# Laser_Teensy5.net
KiCad netlist of a schematic drawn in EAGLE
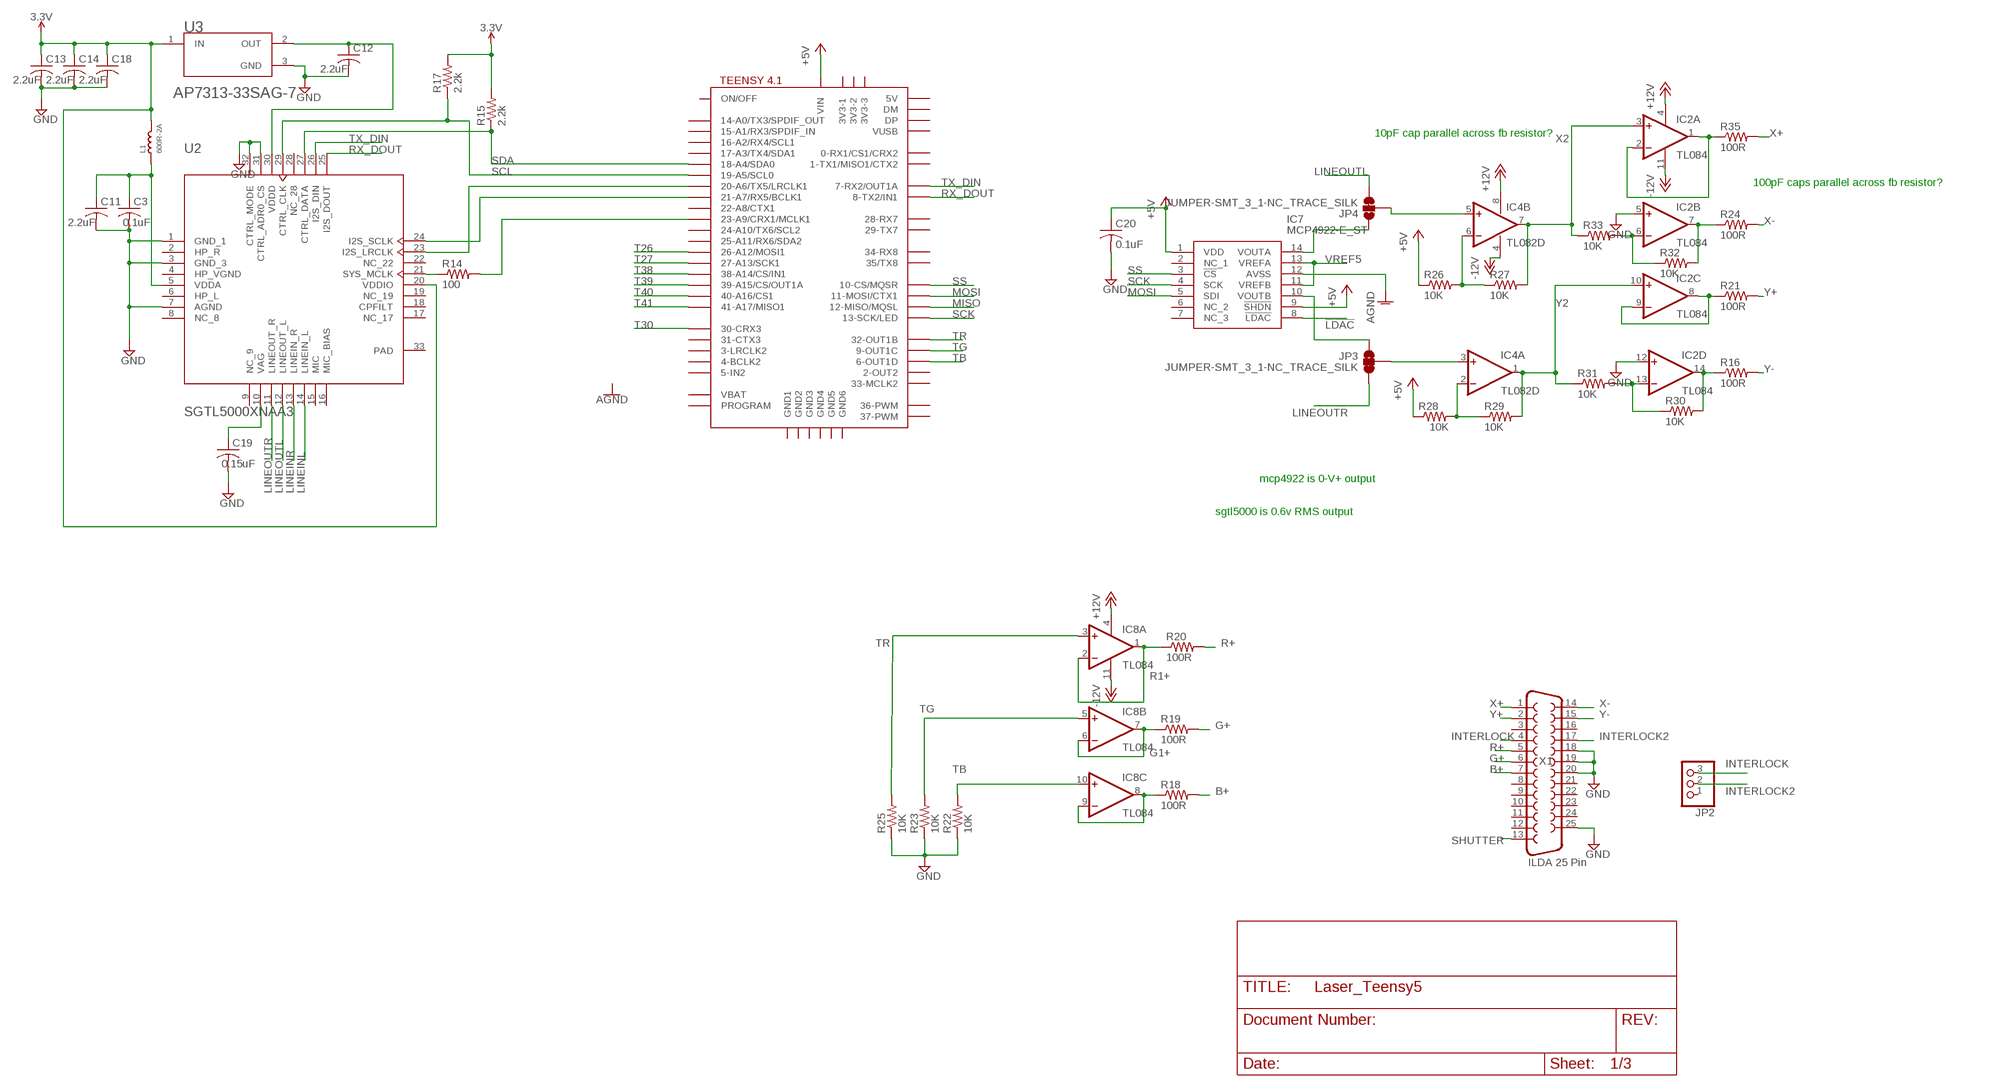
[diagram p0: schematic, sheet 1]
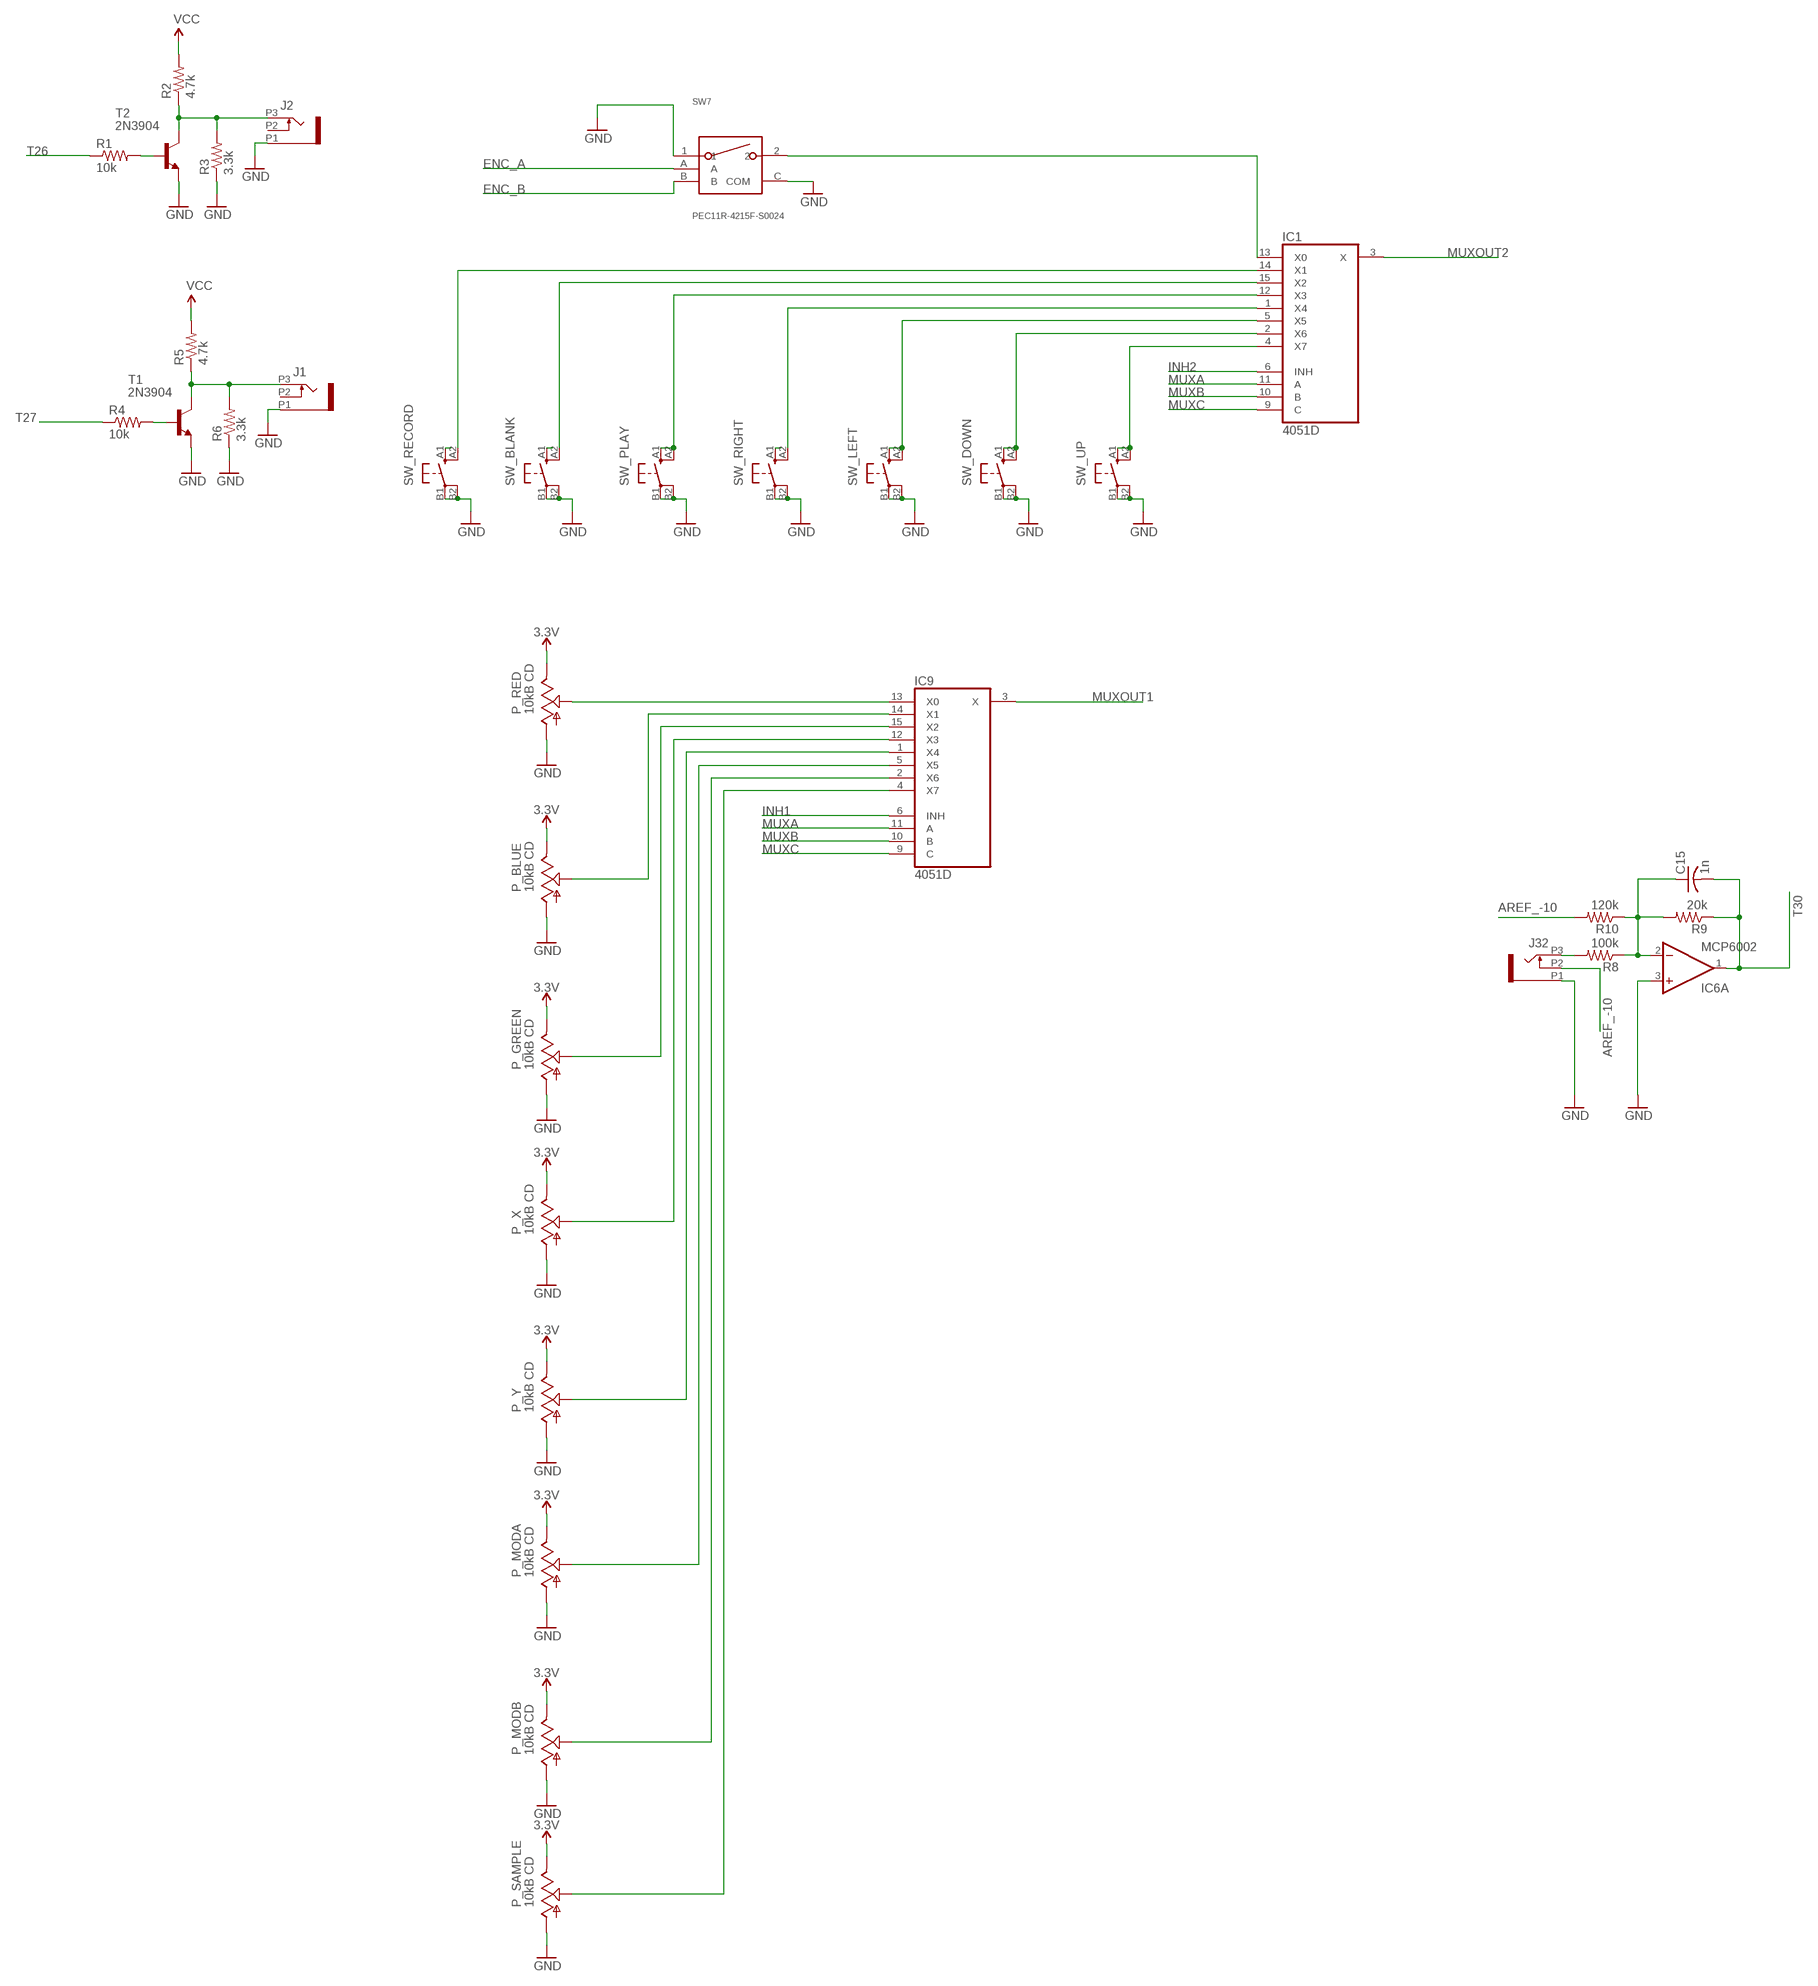
[diagram p1: schematic, sheet 2]
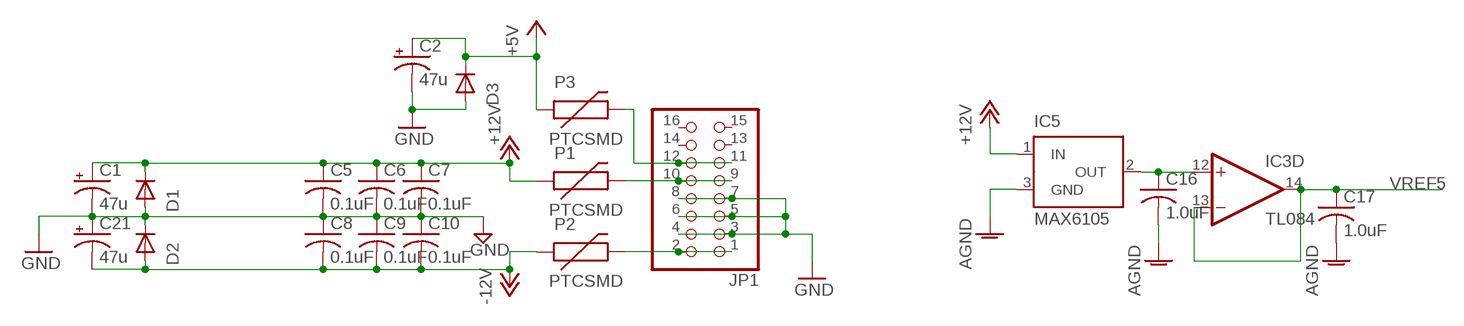
[diagram p2: schematic, sheet 3]

(export (version "E")
  (design (tool "Eeschema 10.0.6"))
  (components
    (comp (ref "C1")
      (value "47u")
      (footprint "eagle-import:PANASONIC_D")
      (libsource (lib "eagle-import") (part "CPOL-USD"))
    )
    (comp (ref "C2")
      (value "47u")
      (footprint "eagle-import:PANASONIC_D")
      (libsource (lib "eagle-import") (part "CPOL-USD"))
    )
    (comp (ref "C5")
      (value "0.1uF")
      (footprint "eagle-import:C0603")
      (libsource (lib "eagle-import") (part "C-USC0603"))
    )
    (comp (ref "C6")
      (value "0.1uF")
      (footprint "eagle-import:C0603")
      (libsource (lib "eagle-import") (part "C-USC0603"))
    )
    (comp (ref "C7")
      (value "0.1uF")
      (footprint "eagle-import:C0603")
      (libsource (lib "eagle-import") (part "C-USC0603"))
    )
    (comp (ref "C8")
      (value "0.1uF")
      (footprint "eagle-import:C0603")
      (libsource (lib "eagle-import") (part "C-USC0603"))
    )
    (comp (ref "C9")
      (value "0.1uF")
      (footprint "eagle-import:C0603")
      (libsource (lib "eagle-import") (part "C-USC0603"))
    )
    (comp (ref "C10")
      (value "0.1uF")
      (footprint "eagle-import:C0603")
      (libsource (lib "eagle-import") (part "C-USC0603"))
    )
    (comp (ref "C16")
      (value "1.0uF")
      (footprint "eagle-import:C025-024X044")
      (libsource (lib "eagle-import") (part "C-US025-024X044"))
    )
    (comp (ref "C17")
      (value "1.0uF")
      (footprint "eagle-import:C025-024X044")
      (libsource (lib "eagle-import") (part "C-US025-024X044"))
    )
    (comp (ref "C21")
      (value "47u")
      (footprint "eagle-import:PANASONIC_D")
      (libsource (lib "eagle-import") (part "CPOL-USD"))
    )
    (comp (ref "D1")
      (value "1N5819HW")
      (footprint "eagle-import:SOD123")
      (libsource (lib "eagle-import") (part "DIODE-SOD123"))
    )
    (comp (ref "D2")
      (value "1N5819HW")
      (footprint "eagle-import:SOD123")
      (libsource (lib "eagle-import") (part "DIODE-SOD123"))
    )
    (comp (ref "D3")
      (value "1N5819HW")
      (footprint "eagle-import:SOD123")
      (libsource (lib "eagle-import") (part "DIODE-SOD123"))
    )
    (comp (ref "IC3")
      (value "TL084")
      (footprint "eagle-import:SOIC-14")
      (libsource (lib "eagle-import") (part "TL084"))
    )
    (comp (ref "IC5")
      (value "MAX6105")
      (footprint "eagle-import:SOT23")
      (libsource (lib "eagle-import") (part "MAX6520"))
    )
    (comp (ref "JP1")
      (value "PINHD-2X8")
      (footprint "eagle-import:2X08")
      (libsource (lib "eagle-import") (part "PINHD-2X8"))
    )
    (comp (ref "P1")
      (value "PTCSMD")
      (footprint "eagle-import:PTC-1206")
      (libsource (lib "eagle-import") (part "PTCSMD"))
    )
    (comp (ref "P2")
      (value "PTCSMD")
      (footprint "eagle-import:PTC-1206")
      (libsource (lib "eagle-import") (part "PTCSMD"))
    )
    (comp (ref "P3")
      (value "PTCSMD")
      (footprint "eagle-import:PTC-1206")
      (libsource (lib "eagle-import") (part "PTCSMD"))
    )
    (comp (ref "C3")
      (value "0.1uF")
      (footprint "eagle-import:RCL_C0603")
      (libsource (lib "eagle-import") (part "RCL_C-USC0603"))
    )
    (comp (ref "C11")
      (value "2.2uF")
      (footprint "eagle-import:RCL_C0603")
      (libsource (lib "eagle-import") (part "RCL_C-USC0603"))
    )
    (comp (ref "C12")
      (value "2.2uF")
      (footprint "eagle-import:RCL_C0603")
      (libsource (lib "eagle-import") (part "RCL_C-USC0603"))
    )
    (comp (ref "C13")
      (value "2.2uF")
      (footprint "eagle-import:RCL_C0603")
      (libsource (lib "eagle-import") (part "RCL_C-USC0603"))
    )
    (comp (ref "C14")
      (value "2.2uF")
      (footprint "eagle-import:RCL_C0603")
      (libsource (lib "eagle-import") (part "RCL_C-USC0603"))
    )
    (comp (ref "C18")
      (value "2.2uF")
      (footprint "eagle-import:RCL_C0603")
      (libsource (lib "eagle-import") (part "RCL_C-USC0603"))
    )
    (comp (ref "C19")
      (value "0.15uF")
      (footprint "eagle-import:RCL_C0603")
      (libsource (lib "eagle-import") (part "RCL_C-USC0603"))
    )
    (comp (ref "C20")
      (value "0.1uF")
      (footprint "eagle-import:C0603")
      (libsource (lib "eagle-import") (part "C-USC0603"))
    )
    (comp (ref "IC2")
      (value "TL084")
      (footprint "eagle-import:SOIC-14")
      (libsource (lib "eagle-import") (part "TL084"))
    )
    (comp (ref "IC4")
      (value "TL082D")
      (footprint "eagle-import:SO08")
      (libsource (lib "eagle-import") (part "TL082D"))
    )
    (comp (ref "IC7")
      (value "MCP4922-E_ST")
      (footprint "eagle-import:SOP65P638X110-14N")
      (fields
        (field (name "ARROW_PART_NUMBER") "MCP4922-E/ST")
        (field (name "MOUSER_PART_NUMBER") "579-MCP4922-E/ST")
      )
      (libsource (lib "eagle-import") (part "MCP4922-E_ST"))
    )
    (comp (ref "IC8")
      (value "TL084")
      (footprint "eagle-import:SOIC-14")
      (libsource (lib "eagle-import") (part "TL084"))
    )
    (comp (ref "JP2")
      (value "PINHD-1X3")
      (footprint "eagle-import:1X03")
      (libsource (lib "eagle-import") (part "PINHD-1X3"))
    )
    (comp (ref "JP3")
      (value "JUMPER-SMT_3_1-NC_TRACE_SILK")
      (footprint "eagle-import:SMT-JUMPER_3_1-NC_TRACE_SILK")
      (libsource (lib "eagle-import") (part "JUMPER-SMT_3_1-NC_TRACE_SILK"))
    )
    (comp (ref "JP4")
      (value "JUMPER-SMT_3_1-NC_TRACE_SILK")
      (footprint "eagle-import:SMT-JUMPER_3_1-NC_TRACE_SILK")
      (libsource (lib "eagle-import") (part "JUMPER-SMT_3_1-NC_TRACE_SILK"))
    )
    (comp (ref "L1")
      (value "600R-2A")
      (footprint "eagle-import:L0805")
      (fields (field (name "MPN") "WLB2012-471T20"))
      (libsource (lib "eagle-import") (part "SMD-FERRITE-BEAD-470R-2A(0805)'0805'"))
    )
    (comp (ref "R14")
      (value "100")
      (footprint "eagle-import:R0603")
      (libsource (lib "eagle-import") (part "resistor_R-US_R0603"))
    )
    (comp (ref "R15")
      (value "2.2k")
      (footprint "eagle-import:R0603")
      (libsource (lib "eagle-import") (part "resistor_R-US_R0603"))
    )
    (comp (ref "R16")
      (value "100R")
      (footprint "eagle-import:R0603")
      (libsource (lib "eagle-import") (part "resistor_R-US_R0603"))
    )
    (comp (ref "R17")
      (value "2.2k")
      (footprint "eagle-import:R0603")
      (libsource (lib "eagle-import") (part "resistor_R-US_R0603"))
    )
    (comp (ref "R18")
      (value "100R")
      (footprint "eagle-import:R0603")
      (libsource (lib "eagle-import") (part "resistor_R-US_R0603"))
    )
    (comp (ref "R19")
      (value "100R")
      (footprint "eagle-import:R0603")
      (libsource (lib "eagle-import") (part "resistor_R-US_R0603"))
    )
    (comp (ref "R20")
      (value "100R")
      (footprint "eagle-import:R0603")
      (libsource (lib "eagle-import") (part "resistor_R-US_R0603"))
    )
    (comp (ref "R21")
      (value "100R")
      (footprint "eagle-import:R0603")
      (libsource (lib "eagle-import") (part "resistor_R-US_R0603"))
    )
    (comp (ref "R22")
      (value "10K")
      (footprint "eagle-import:R0603")
      (libsource (lib "eagle-import") (part "resistor_R-US_R0603"))
    )
    (comp (ref "R23")
      (value "10K")
      (footprint "eagle-import:R0603")
      (libsource (lib "eagle-import") (part "resistor_R-US_R0603"))
    )
    (comp (ref "R24")
      (value "100R")
      (footprint "eagle-import:R0603")
      (libsource (lib "eagle-import") (part "resistor_R-US_R0603"))
    )
    (comp (ref "R25")
      (value "10K")
      (footprint "eagle-import:R0603")
      (libsource (lib "eagle-import") (part "resistor_R-US_R0603"))
    )
    (comp (ref "R26")
      (value "10K")
      (footprint "eagle-import:R0603")
      (libsource (lib "eagle-import") (part "resistor_R-US_R0603"))
    )
    (comp (ref "R27")
      (value "10K")
      (footprint "eagle-import:R0603")
      (libsource (lib "eagle-import") (part "resistor_R-US_R0603"))
    )
    (comp (ref "R28")
      (value "10K")
      (footprint "eagle-import:R0603")
      (libsource (lib "eagle-import") (part "resistor_R-US_R0603"))
    )
    (comp (ref "R29")
      (value "10K")
      (footprint "eagle-import:R0603")
      (libsource (lib "eagle-import") (part "resistor_R-US_R0603"))
    )
    (comp (ref "R30")
      (value "10K")
      (footprint "eagle-import:R0603")
      (libsource (lib "eagle-import") (part "resistor_R-US_R0603"))
    )
    (comp (ref "R31")
      (value "10K")
      (footprint "eagle-import:R0603")
      (libsource (lib "eagle-import") (part "resistor_R-US_R0603"))
    )
    (comp (ref "R32")
      (value "10K")
      (footprint "eagle-import:R0603")
      (libsource (lib "eagle-import") (part "resistor_R-US_R0603"))
    )
    (comp (ref "R33")
      (value "10K")
      (footprint "eagle-import:R0603")
      (libsource (lib "eagle-import") (part "resistor_R-US_R0603"))
    )
    (comp (ref "R35")
      (value "100R")
      (footprint "eagle-import:R0603")
      (libsource (lib "eagle-import") (part "resistor_R-US_R0603"))
    )
    (comp (ref "U$2")
      (value "TEENSY41-E")
      (footprint "eagle-import:TENNSY41-E")
      (libsource (lib "eagle-import") (part "TEENSY41-E"))
    )
    (comp (ref "U2")
      (value "SGTL5000XNAA3")
      (footprint "eagle-import:QFN-32")
      (fields
        (field (name "DIGIKEY_PART_NUMBER") "SGTL5000XNAA3-ND")
        (field (name "MANUFACTURER") "NXP USA Inc.")
        (field (name "CREATED_BY") "PCBLayout.com")
      )
      (libsource (lib "eagle-import") (part "SGTL5000XNAA3"))
    )
    (comp (ref "U3")
      (value "DIODES_INC_AP7313-33SAG-7DIODES_INC_AP7313-33SAG-7_0_3")
      (footprint "eagle-import:DIODES_INC_AP7313-33SAG-7_3")
      (fields
        (field (name "DIGIKEY_PART_NUMBER") "AP7313-33SAG-7DICT-ND")
        (field (name "MF") "Diodes Inc.")
        (field (name "MOUSER_PART_NUMBER") "621-AP7313-33SAG-7")
      )
      (libsource (lib "eagle-import") (part "DIODES_INC_AP7313-33SAG-7DIODES_INC_AP7313-33SAG-7_0_3"))
    )
    (comp (ref "X1")
      (value "ILDA 25 Pin")
      (footprint "eagle-import:F25D")
      (libsource (lib "eagle-import") (part "F25D"))
    )
    (comp (ref "C15")
      (value "1n")
      (footprint "eagle-import:C050-025X075")
      (libsource (lib "eagle-import") (part "rcl_334_C-US050-025X075"))
    )
    (comp (ref "IC1")
      (value "4051D")
      (footprint "eagle-import:SO16")
      (libsource (lib "eagle-import") (part "4051D"))
    )
    (comp (ref "IC6")
      (value "MCP6002")
      (footprint "eagle-import:SO08")
      (libsource (lib "eagle-import") (part "TL072D"))
    )
    (comp (ref "IC9")
      (value "4051D")
      (footprint "eagle-import:SO16")
      (libsource (lib "eagle-import") (part "4051D"))
    )
    (comp (ref "J1")
      (value "PJ301_THONKICONN6")
      (footprint "eagle-import:WQP_PJ_301M6")
      (libsource (lib "eagle-import") (part "PJ301_THONKICONN6"))
    )
    (comp (ref "J2")
      (value "PJ301_THONKICONN6")
      (footprint "eagle-import:WQP_PJ_301M6")
      (libsource (lib "eagle-import") (part "PJ301_THONKICONN6"))
    )
    (comp (ref "J32")
      (value "PJ301_THONKICONN6")
      (footprint "eagle-import:WQP_PJ_301M6")
      (libsource (lib "eagle-import") (part "PJ301_THONKICONN6"))
    )
    (comp (ref "P_BLUE")
      (value "10kB CD")
      (footprint "eagle-import:ALPS_POT_VERTICAL_PS")
      (libsource (lib "eagle-import") (part "POT_USVERTICAL_PS"))
    )
    (comp (ref "P_GREEN")
      (value "10kB CD")
      (footprint "eagle-import:ALPS_POT_VERTICAL_PS")
      (libsource (lib "eagle-import") (part "POT_USVERTICAL_PS"))
    )
    (comp (ref "P_MODA")
      (value "10kB CD")
      (footprint "eagle-import:ALPS_POT_VERTICAL_PS")
      (libsource (lib "eagle-import") (part "POT_USVERTICAL_PS"))
    )
    (comp (ref "P_MODB")
      (value "10kB CD")
      (footprint "eagle-import:ALPS_POT_VERTICAL_PS")
      (libsource (lib "eagle-import") (part "POT_USVERTICAL_PS"))
    )
    (comp (ref "P_RED")
      (value "10kB CD")
      (footprint "eagle-import:ALPS_POT_VERTICAL_PS")
      (libsource (lib "eagle-import") (part "POT_USVERTICAL_PS"))
    )
    (comp (ref "P_SAMPLE")
      (value "10kB CD")
      (footprint "eagle-import:ALPS_POT_VERTICAL_PS")
      (libsource (lib "eagle-import") (part "POT_USVERTICAL_PS"))
    )
    (comp (ref "P_X")
      (value "10kB CD")
      (footprint "eagle-import:ALPS_POT_VERTICAL_PS")
      (libsource (lib "eagle-import") (part "POT_USVERTICAL_PS"))
    )
    (comp (ref "P_Y")
      (value "10kB CD")
      (footprint "eagle-import:ALPS_POT_VERTICAL_PS")
      (libsource (lib "eagle-import") (part "POT_USVERTICAL_PS"))
    )
    (comp (ref "R1")
      (value "10k")
      (footprint "eagle-import:0204_7")
      (libsource (lib "eagle-import") (part "R-US_0204/7"))
    )
    (comp (ref "R2")
      (value "4.7k")
      (footprint "eagle-import:0204_7")
      (libsource (lib "eagle-import") (part "R-US_0204/7"))
    )
    (comp (ref "R3")
      (value "3.3k")
      (footprint "eagle-import:0204_7")
      (libsource (lib "eagle-import") (part "R-US_0204/7"))
    )
    (comp (ref "R4")
      (value "10k")
      (footprint "eagle-import:0204_7")
      (libsource (lib "eagle-import") (part "R-US_0204/7"))
    )
    (comp (ref "R5")
      (value "4.7k")
      (footprint "eagle-import:0204_7")
      (libsource (lib "eagle-import") (part "R-US_0204/7"))
    )
    (comp (ref "R6")
      (value "3.3k")
      (footprint "eagle-import:0204_7")
      (libsource (lib "eagle-import") (part "R-US_0204/7"))
    )
    (comp (ref "R8")
      (value "100k")
      (footprint "eagle-import:0204_7")
      (libsource (lib "eagle-import") (part "R-US_0204/7"))
    )
    (comp (ref "R9")
      (value "20k")
      (footprint "eagle-import:0204_7")
      (libsource (lib "eagle-import") (part "R-US_0204/7"))
    )
    (comp (ref "R10")
      (value "120k")
      (footprint "eagle-import:0204_7")
      (libsource (lib "eagle-import") (part "R-US_0204/7"))
    )
    (comp (ref "SW7")
      (value "PEC11R-4215F-S0024")
      (footprint "eagle-import:PEC11R-4215F-S0024")
      (fields
        (field (name "DIGIKEY_PART_NUMBER") "PEC11R-4215F-S0024-ND")
        (field (name "MANUFACTURER") "Bourns Inc.")
        (field (name "CREATED_BY") "PCBLayout.com")
      )
      (libsource (lib "eagle-import") (part "PEC11R-4215F-S0024"))
    )
    (comp (ref "SW_BLANK")
      (value "D6R")
      (footprint "eagle-import:D6R")
      (libsource (lib "eagle-import") (part "D6R"))
    )
    (comp (ref "SW_DOWN")
      (value "D6R")
      (footprint "eagle-import:D6R")
      (libsource (lib "eagle-import") (part "D6R"))
    )
    (comp (ref "SW_LEFT")
      (value "D6R")
      (footprint "eagle-import:D6R")
      (libsource (lib "eagle-import") (part "D6R"))
    )
    (comp (ref "SW_PLAY")
      (value "D6R")
      (footprint "eagle-import:D6R")
      (libsource (lib "eagle-import") (part "D6R"))
    )
    (comp (ref "SW_RECORD")
      (value "D6R")
      (footprint "eagle-import:D6R")
      (libsource (lib "eagle-import") (part "D6R"))
    )
    (comp (ref "SW_RIGHT")
      (value "D6R")
      (footprint "eagle-import:D6R")
      (libsource (lib "eagle-import") (part "D6R"))
    )
    (comp (ref "SW_UP")
      (value "D6R")
      (footprint "eagle-import:D6R")
      (libsource (lib "eagle-import") (part "D6R"))
    )
    (comp (ref "T1")
      (value "2N3904")
      (footprint "eagle-import:TO92")
      (libsource (lib "eagle-import") (part "2N3904"))
    )
    (comp (ref "T2")
      (value "2N3904")
      (footprint "eagle-import:TO92")
      (libsource (lib "eagle-import") (part "2N3904"))
    )
  )
  (nets
    (net (code "1") (name "+5V") (class "Default")
      (node (ref "C2") (pin "+") (pinfunction "+_+") (pintype "passive"))
      (node (ref "C20") (pin "1") (pinfunction "1_1") (pintype "passive"))
      (node (ref "D3") (pin "C") (pinfunction "C_C") (pintype "passive"))
      (node (ref "IC7") (pin "1") (pinfunction "VDD_1") (pintype "bidirectional"))
      (node (ref "IC7") (pin "9") (pinfunction "~{SHDN}_9") (pintype "bidirectional"))
      (node (ref "P3") (pin "1") (pinfunction "1_1") (pintype "bidirectional"))
      (node (ref "R26") (pin "1") (pinfunction "1_1") (pintype "passive"))
      (node (ref "R28") (pin "1") (pinfunction "1_1") (pintype "passive"))
      (node (ref "U$2") (pin "VIN") (pinfunction "VIN_VIN") (pintype "bidirectional"))
    )
    (net (code "2") (name "+12V") (class "Default")
      (node (ref "C1") (pin "+") (pinfunction "+_+") (pintype "passive"))
      (node (ref "C5") (pin "1") (pinfunction "1_1") (pintype "passive"))
      (node (ref "C6") (pin "1") (pinfunction "1_1") (pintype "passive"))
      (node (ref "C7") (pin "1") (pinfunction "1_1") (pintype "passive"))
      (node (ref "D1") (pin "C") (pinfunction "C_C") (pintype "passive"))
      (node (ref "IC2") (pin "4") (pinfunction "V+_4") (pintype "power_in"))
      (node (ref "IC4") (pin "8") (pinfunction "V+_8") (pintype "power_in"))
      (node (ref "IC5") (pin "1") (pinfunction "IN_1") (pintype "input"))
      (node (ref "IC8") (pin "4") (pinfunction "V+_4") (pintype "power_in"))
      (node (ref "P1") (pin "1") (pinfunction "1_1") (pintype "bidirectional"))
    )
    (net (code "3") (name "-12V") (class "Default")
      (node (ref "C10") (pin "2") (pinfunction "2_2") (pintype "passive"))
      (node (ref "C21") (pin "-") (pinfunction "-_-") (pintype "passive"))
      (node (ref "C8") (pin "2") (pinfunction "2_2") (pintype "passive"))
      (node (ref "C9") (pin "2") (pinfunction "2_2") (pintype "passive"))
      (node (ref "D2") (pin "A") (pinfunction "A_A") (pintype "passive"))
      (node (ref "IC2") (pin "11") (pinfunction "V-_11") (pintype "power_in"))
      (node (ref "IC4") (pin "4") (pinfunction "V-_4") (pintype "power_in"))
      (node (ref "IC8") (pin "11") (pinfunction "V-_11") (pintype "power_in"))
      (node (ref "P2") (pin "1") (pinfunction "1_1") (pintype "bidirectional"))
    )
    (net (code "4") (name "3.3V") (class "Default")
      (node (ref "C13") (pin "1") (pinfunction "1_1") (pintype "passive"))
      (node (ref "C14") (pin "1") (pinfunction "1_1") (pintype "passive"))
      (node (ref "C18") (pin "1") (pinfunction "1_1") (pintype "passive"))
      (node (ref "L1") (pin "2") (pinfunction "2_2") (pintype "passive"))
      (node (ref "P_BLUE") (pin "P$1") (pinfunction "E_P$1") (pintype "passive"))
      (node (ref "P_GREEN") (pin "P$1") (pinfunction "E_P$1") (pintype "passive"))
      (node (ref "P_MODA") (pin "P$1") (pinfunction "E_P$1") (pintype "passive"))
      (node (ref "P_MODB") (pin "P$1") (pinfunction "E_P$1") (pintype "passive"))
      (node (ref "P_RED") (pin "P$1") (pinfunction "E_P$1") (pintype "passive"))
      (node (ref "P_SAMPLE") (pin "P$1") (pinfunction "E_P$1") (pintype "passive"))
      (node (ref "P_X") (pin "P$1") (pinfunction "E_P$1") (pintype "passive"))
      (node (ref "P_Y") (pin "P$1") (pinfunction "E_P$1") (pintype "passive"))
      (node (ref "R15") (pin "2") (pinfunction "2_2") (pintype "passive"))
      (node (ref "R17") (pin "2") (pinfunction "2_2") (pintype "passive"))
      (node (ref "U2") (pin "20") (pinfunction "VDDIO_20") (pintype "power_in"))
      (node (ref "U3") (pin "1") (pinfunction "IN_1") (pintype "power_in"))
    )
    (net (code "5") (name "AGND") (class "Default")
      (node (ref "C16") (pin "2") (pinfunction "2_2") (pintype "passive"))
      (node (ref "C17") (pin "2") (pinfunction "2_2") (pintype "passive"))
      (node (ref "IC5") (pin "3") (pinfunction "GND_3") (pintype "power_in"))
      (node (ref "IC7") (pin "12") (pinfunction "AVSS_12") (pintype "bidirectional"))
    )
    (net (code "6") (name "AREF_-10") (class "Default")
      (node (ref "J32") (pin "P2") (pinfunction "2_P2") (pintype "passive"))
      (node (ref "R10") (pin "2") (pinfunction "2_2") (pintype "passive"))
    )
    (net (code "7") (name "B+") (class "Default")
      (node (ref "R18") (pin "2") (pinfunction "2_2") (pintype "passive"))
      (node (ref "X1") (pin "7") (pinfunction "7_7") (pintype "passive"))
    )
    (net (code "8") (name "ENC_A") (class "Default")
      (node (ref "SW7") (pin "A") (pinfunction "A_A") (pintype "passive"))
    )
    (net (code "9") (name "ENC_B") (class "Default")
      (node (ref "SW7") (pin "B") (pinfunction "B_B") (pintype "passive"))
    )
    (net (code "10") (name "G+") (class "Default")
      (node (ref "R19") (pin "2") (pinfunction "2_2") (pintype "passive"))
      (node (ref "X1") (pin "6") (pinfunction "6_6") (pintype "passive"))
    )
    (net (code "11") (name "G1+") (class "Default")
      (node (ref "IC8") (pin "6") (pinfunction "-IN_6") (pintype "input"))
      (node (ref "IC8") (pin "7") (pinfunction "OUT_7") (pintype "output"))
      (node (ref "R19") (pin "1") (pinfunction "1_1") (pintype "passive"))
    )
    (net (code "12") (name "GND") (class "Default")
      (node (ref "C1") (pin "-") (pinfunction "-_-") (pintype "passive"))
      (node (ref "C10") (pin "1") (pinfunction "1_1") (pintype "passive"))
      (node (ref "C11") (pin "2") (pinfunction "2_2") (pintype "passive"))
      (node (ref "C12") (pin "2") (pinfunction "2_2") (pintype "passive"))
      (node (ref "C13") (pin "2") (pinfunction "2_2") (pintype "passive"))
      (node (ref "C14") (pin "2") (pinfunction "2_2") (pintype "passive"))
      (node (ref "C18") (pin "2") (pinfunction "2_2") (pintype "passive"))
      (node (ref "C19") (pin "2") (pinfunction "2_2") (pintype "passive"))
      (node (ref "C2") (pin "-") (pinfunction "-_-") (pintype "passive"))
      (node (ref "C20") (pin "2") (pinfunction "2_2") (pintype "passive"))
      (node (ref "C21") (pin "+") (pinfunction "+_+") (pintype "passive"))
      (node (ref "C3") (pin "2") (pinfunction "2_2") (pintype "passive"))
      (node (ref "C5") (pin "2") (pinfunction "2_2") (pintype "passive"))
      (node (ref "C6") (pin "2") (pinfunction "2_2") (pintype "passive"))
      (node (ref "C7") (pin "2") (pinfunction "2_2") (pintype "passive"))
      (node (ref "C8") (pin "1") (pinfunction "1_1") (pintype "passive"))
      (node (ref "C9") (pin "1") (pinfunction "1_1") (pintype "passive"))
      (node (ref "D1") (pin "A") (pinfunction "A_A") (pintype "passive"))
      (node (ref "D2") (pin "C") (pinfunction "C_C") (pintype "passive"))
      (node (ref "D3") (pin "A") (pinfunction "A_A") (pintype "passive"))
      (node (ref "IC2") (pin "12") (pinfunction "+IN_12") (pintype "input"))
      (node (ref "IC2") (pin "5") (pinfunction "+IN_5") (pintype "input"))
      (node (ref "IC6") (pin "3") (pinfunction "+IN_3") (pintype "input"))
      (node (ref "J1") (pin "P1") (pinfunction "1_P1") (pintype "passive"))
      (node (ref "J2") (pin "P1") (pinfunction "1_P1") (pintype "passive"))
      (node (ref "J32") (pin "P1") (pinfunction "1_P1") (pintype "passive"))
      (node (ref "JP1") (pin "3") (pinfunction "3_3") (pintype "passive"))
      (node (ref "JP1") (pin "4") (pinfunction "4_4") (pintype "passive"))
      (node (ref "JP1") (pin "5") (pinfunction "5_5") (pintype "passive"))
      (node (ref "JP1") (pin "6") (pinfunction "6_6") (pintype "passive"))
      (node (ref "JP1") (pin "7") (pinfunction "7_7") (pintype "passive"))
      (node (ref "JP1") (pin "8") (pinfunction "8_8") (pintype "passive"))
      (node (ref "P_BLUE") (pin "P$3") (pinfunction "A_P$3") (pintype "passive"))
      (node (ref "P_GREEN") (pin "P$3") (pinfunction "A_P$3") (pintype "passive"))
      (node (ref "P_MODA") (pin "P$3") (pinfunction "A_P$3") (pintype "passive"))
      (node (ref "P_MODB") (pin "P$3") (pinfunction "A_P$3") (pintype "passive"))
      (node (ref "P_RED") (pin "P$3") (pinfunction "A_P$3") (pintype "passive"))
      (node (ref "P_SAMPLE") (pin "P$3") (pinfunction "A_P$3") (pintype "passive"))
      (node (ref "P_X") (pin "P$3") (pinfunction "A_P$3") (pintype "passive"))
      (node (ref "P_Y") (pin "P$3") (pinfunction "A_P$3") (pintype "passive"))
      (node (ref "R22") (pin "1") (pinfunction "1_1") (pintype "passive"))
      (node (ref "R23") (pin "1") (pinfunction "1_1") (pintype "passive"))
      (node (ref "R25") (pin "1") (pinfunction "1_1") (pintype "passive"))
      (node (ref "R3") (pin "1") (pinfunction "1_1") (pintype "passive"))
      (node (ref "R6") (pin "1") (pinfunction "1_1") (pintype "passive"))
      (node (ref "SW7") (pin "1") (pinfunction "1_1") (pintype "passive"))
      (node (ref "SW7") (pin "C") (pinfunction "COM_C") (pintype "passive"))
      (node (ref "SW_BLANK") (pin "B2") (pinfunction "P1_B2") (pintype "passive"))
      (node (ref "SW_DOWN") (pin "B1") (pinfunction "P_B1") (pintype "passive"))
      (node (ref "SW_DOWN") (pin "B2") (pinfunction "P1_B2") (pintype "passive"))
      (node (ref "SW_LEFT") (pin "B1") (pinfunction "P_B1") (pintype "passive"))
      (node (ref "SW_LEFT") (pin "B2") (pinfunction "P1_B2") (pintype "passive"))
      (node (ref "SW_PLAY") (pin "B1") (pinfunction "P_B1") (pintype "passive"))
      (node (ref "SW_PLAY") (pin "B2") (pinfunction "P1_B2") (pintype "passive"))
      (node (ref "SW_RECORD") (pin "B2") (pinfunction "P1_B2") (pintype "passive"))
      (node (ref "SW_RIGHT") (pin "B2") (pinfunction "P1_B2") (pintype "passive"))
      (node (ref "SW_UP") (pin "B1") (pinfunction "P_B1") (pintype "passive"))
      (node (ref "SW_UP") (pin "B2") (pinfunction "P1_B2") (pintype "passive"))
      (node (ref "T1") (pin "3") (pinfunction "E_3") (pintype "passive"))
      (node (ref "T2") (pin "3") (pinfunction "E_3") (pintype "passive"))
      (node (ref "U2") (pin "1") (pinfunction "GND_1_1") (pintype "power_in"))
      (node (ref "U2") (pin "3") (pinfunction "GND_3_3") (pintype "power_in"))
      (node (ref "U2") (pin "31") (pinfunction "CTRL_ADR0_CS_31") (pintype "input"))
      (node (ref "U2") (pin "32") (pinfunction "CTRL_MODE_32") (pintype "bidirectional"))
      (node (ref "U2") (pin "7") (pinfunction "AGND_7") (pintype "power_in"))
      (node (ref "U3") (pin "3") (pinfunction "GND_3") (pintype "power_in"))
      (node (ref "X1") (pin "18") (pinfunction "18_18") (pintype "passive"))
      (node (ref "X1") (pin "19") (pinfunction "19_19") (pintype "passive"))
      (node (ref "X1") (pin "20") (pinfunction "20_20") (pintype "passive"))
      (node (ref "X1") (pin "25") (pinfunction "25_25") (pintype "passive"))
    )
    (net (code "13") (name "HP_VGND") (class "Default")
      (node (ref "U2") (pin "4") (pinfunction "HP_VGND_4") (pintype "power_in"))
    )
    (net (code "14") (name "INH1") (class "Default")
      (node (ref "IC9") (pin "6") (pinfunction "INH_6") (pintype "input"))
    )
    (net (code "15") (name "INH2") (class "Default")
      (node (ref "IC1") (pin "6") (pinfunction "INH_6") (pintype "input"))
    )
    (net (code "16") (name "INTERLOCK") (class "Default")
      (node (ref "JP2") (pin "3") (pinfunction "3_3") (pintype "passive"))
      (node (ref "X1") (pin "4") (pinfunction "4_4") (pintype "passive"))
    )
    (net (code "17") (name "INTERLOCK2") (class "Default")
      (node (ref "JP2") (pin "2") (pinfunction "2_2") (pintype "passive"))
      (node (ref "X1") (pin "17") (pinfunction "17_17") (pintype "passive"))
    )
    (net (code "18") (name "LINEINL") (class "Default")
      (node (ref "U2") (pin "14") (pinfunction "LINEIN_L_14") (pintype "input"))
    )
    (net (code "19") (name "LINEINR") (class "Default")
      (node (ref "U2") (pin "13") (pinfunction "LINEIN_R_13") (pintype "input"))
    )
    (net (code "20") (name "LINEOUTL") (class "Default")
      (node (ref "JP4") (pin "3") (pinfunction "3_3") (pintype "passive"))
      (node (ref "U2") (pin "12") (pinfunction "LINEOUT_L_12") (pintype "output"))
    )
    (net (code "21") (name "LINEOUTR") (class "Default")
      (node (ref "JP3") (pin "3") (pinfunction "3_3") (pintype "passive"))
      (node (ref "U2") (pin "11") (pinfunction "LINEOUT_R_11") (pintype "output"))
    )
    (net (code "22") (name "MISO") (class "Default")
      (node (ref "U$2") (pin "12-MISO/MQSL") (pinfunction "12-MISO/MQSL_12-MISO/MQSL") (pintype "bidirectional"))
    )
    (net (code "23") (name "MOSI") (class "Default")
      (node (ref "IC7") (pin "5") (pinfunction "SDI_5") (pintype "bidirectional"))
      (node (ref "U$2") (pin "11-MOSI/CTX1") (pinfunction "11-MOSI/CTX1_11-MOSI/CTX1") (pintype "bidirectional"))
    )
    (net (code "24") (name "MUXA") (class "Default")
      (node (ref "IC1") (pin "11") (pinfunction "A_11") (pintype "input"))
      (node (ref "IC9") (pin "11") (pinfunction "A_11") (pintype "input"))
    )
    (net (code "25") (name "MUXB") (class "Default")
      (node (ref "IC1") (pin "10") (pinfunction "B_10") (pintype "input"))
      (node (ref "IC9") (pin "10") (pinfunction "B_10") (pintype "input"))
    )
    (net (code "26") (name "MUXC") (class "Default")
      (node (ref "IC1") (pin "9") (pinfunction "C_9") (pintype "input"))
      (node (ref "IC9") (pin "9") (pinfunction "C_9") (pintype "input"))
    )
    (net (code "27") (name "MUXOUT1") (class "Default")
      (node (ref "IC9") (pin "3") (pinfunction "X_3") (pintype "bidirectional"))
    )
    (net (code "28") (name "MUXOUT2") (class "Default")
      (node (ref "IC1") (pin "3") (pinfunction "X_3") (pintype "bidirectional"))
    )
    (net (code "29") (name "Net-(IC1A-X0)") (class "Default")
      (node (ref "IC1") (pin "13") (pinfunction "X0_13") (pintype "bidirectional"))
      (node (ref "SW7") (pin "2") (pinfunction "2_2") (pintype "passive"))
    )
    (net (code "30") (name "Net-(IC1A-X1)") (class "Default")
      (node (ref "IC1") (pin "14") (pinfunction "X1_14") (pintype "bidirectional"))
      (node (ref "SW_RECORD") (pin "A2") (pinfunction "S1_A2") (pintype "passive"))
    )
    (net (code "31") (name "Net-(IC1A-X2)") (class "Default")
      (node (ref "IC1") (pin "15") (pinfunction "X2_15") (pintype "bidirectional"))
      (node (ref "SW_BLANK") (pin "A2") (pinfunction "S1_A2") (pintype "passive"))
    )
    (net (code "32") (name "Net-(IC1A-X4)") (class "Default")
      (node (ref "IC1") (pin "1") (pinfunction "X4_1") (pintype "bidirectional"))
      (node (ref "SW_RIGHT") (pin "A2") (pinfunction "S1_A2") (pintype "passive"))
    )
    (net (code "33") (name "Net-(IC2A--IN)") (class "Default")
      (node (ref "IC2") (pin "1") (pinfunction "OUT_1") (pintype "output"))
      (node (ref "IC2") (pin "2") (pinfunction "-IN_2") (pintype "input"))
      (node (ref "R35") (pin "1") (pinfunction "1_1") (pintype "passive"))
    )
    (net (code "34") (name "Net-(IC2B--IN)") (class "Default")
      (node (ref "IC2") (pin "6") (pinfunction "-IN_6") (pintype "input"))
      (node (ref "R32") (pin "1") (pinfunction "1_1") (pintype "passive"))
      (node (ref "R33") (pin "2") (pinfunction "2_2") (pintype "passive"))
    )
    (net (code "35") (name "Net-(IC2B-OUT)") (class "Default")
      (node (ref "IC2") (pin "7") (pinfunction "OUT_7") (pintype "output"))
      (node (ref "R24") (pin "1") (pinfunction "1_1") (pintype "passive"))
      (node (ref "R32") (pin "2") (pinfunction "2_2") (pintype "passive"))
    )
    (net (code "36") (name "Net-(IC2C--IN)") (class "Default")
      (node (ref "IC2") (pin "8") (pinfunction "OUT_8") (pintype "output"))
      (node (ref "IC2") (pin "9") (pinfunction "-IN_9") (pintype "input"))
      (node (ref "R21") (pin "1") (pinfunction "1_1") (pintype "passive"))
    )
    (net (code "37") (name "Net-(IC2D--IN)") (class "Default")
      (node (ref "IC2") (pin "13") (pinfunction "-IN_13") (pintype "input"))
      (node (ref "R30") (pin "1") (pinfunction "1_1") (pintype "passive"))
      (node (ref "R31") (pin "2") (pinfunction "2_2") (pintype "passive"))
    )
    (net (code "38") (name "Net-(IC2D-OUT)") (class "Default")
      (node (ref "IC2") (pin "14") (pinfunction "OUT_14") (pintype "output"))
      (node (ref "R16") (pin "1") (pinfunction "1_1") (pintype "passive"))
      (node (ref "R30") (pin "2") (pinfunction "2_2") (pintype "passive"))
    )
    (net (code "39") (name "Net-(IC3D-+IN)") (class "Default")
      (node (ref "C16") (pin "1") (pinfunction "1_1") (pintype "passive"))
      (node (ref "IC3") (pin "12") (pinfunction "+IN_12") (pintype "input"))
      (node (ref "IC5") (pin "2") (pinfunction "OUT_2") (pintype "input"))
    )
    (net (code "40") (name "Net-(IC4A-+IN)") (class "Default")
      (node (ref "IC4") (pin "3") (pinfunction "+IN_3") (pintype "input"))
      (node (ref "JP3") (pin "2") (pinfunction "2_2") (pintype "passive"))
    )
    (net (code "41") (name "Net-(IC4A--IN)") (class "Default")
      (node (ref "IC4") (pin "2") (pinfunction "-IN_2") (pintype "input"))
      (node (ref "R28") (pin "2") (pinfunction "2_2") (pintype "passive"))
      (node (ref "R29") (pin "1") (pinfunction "1_1") (pintype "passive"))
    )
    (net (code "42") (name "Net-(IC4B-+IN)") (class "Default")
      (node (ref "IC4") (pin "5") (pinfunction "+IN_5") (pintype "input"))
      (node (ref "JP4") (pin "2") (pinfunction "2_2") (pintype "passive"))
    )
    (net (code "43") (name "Net-(IC4B--IN)") (class "Default")
      (node (ref "IC4") (pin "6") (pinfunction "-IN_6") (pintype "input"))
      (node (ref "R26") (pin "2") (pinfunction "2_2") (pintype "passive"))
      (node (ref "R27") (pin "1") (pinfunction "1_1") (pintype "passive"))
    )
    (net (code "44") (name "Net-(IC6A--IN)") (class "Default")
      (node (ref "C15") (pin "1") (pinfunction "1_1") (pintype "passive"))
      (node (ref "IC6") (pin "2") (pinfunction "-IN_2") (pintype "input"))
      (node (ref "R10") (pin "1") (pinfunction "1_1") (pintype "passive"))
      (node (ref "R8") (pin "1") (pinfunction "1_1") (pintype "passive"))
      (node (ref "R9") (pin "2") (pinfunction "2_2") (pintype "passive"))
    )
    (net (code "45") (name "Net-(IC7-VOUTA)") (class "Default")
      (node (ref "IC7") (pin "14") (pinfunction "VOUTA_14") (pintype "bidirectional"))
      (node (ref "JP4") (pin "1") (pinfunction "1_1") (pintype "passive"))
    )
    (net (code "46") (name "Net-(IC7-VOUTB)") (class "Default")
      (node (ref "IC7") (pin "10") (pinfunction "VOUTB_10") (pintype "bidirectional"))
      (node (ref "JP3") (pin "1") (pinfunction "1_1") (pintype "passive"))
    )
    (net (code "47") (name "Net-(IC8C--IN)") (class "Default")
      (node (ref "IC8") (pin "8") (pinfunction "OUT_8") (pintype "output"))
      (node (ref "IC8") (pin "9") (pinfunction "-IN_9") (pintype "input"))
      (node (ref "R18") (pin "1") (pinfunction "1_1") (pintype "passive"))
    )
    (net (code "48") (name "Net-(IC9A-X0)") (class "Default")
      (node (ref "IC9") (pin "13") (pinfunction "X0_13") (pintype "bidirectional"))
      (node (ref "P_RED") (pin "P$2") (pinfunction "S_P$2") (pintype "passive"))
    )
    (net (code "49") (name "Net-(IC9A-X1)") (class "Default")
      (node (ref "IC9") (pin "14") (pinfunction "X1_14") (pintype "bidirectional"))
      (node (ref "P_BLUE") (pin "P$2") (pinfunction "S_P$2") (pintype "passive"))
    )
    (net (code "50") (name "Net-(IC9A-X2)") (class "Default")
      (node (ref "IC9") (pin "15") (pinfunction "X2_15") (pintype "bidirectional"))
      (node (ref "P_GREEN") (pin "P$2") (pinfunction "S_P$2") (pintype "passive"))
    )
    (net (code "51") (name "Net-(IC9A-X3)") (class "Default")
      (node (ref "IC9") (pin "12") (pinfunction "X3_12") (pintype "bidirectional"))
      (node (ref "P_X") (pin "P$2") (pinfunction "S_P$2") (pintype "passive"))
    )
    (net (code "52") (name "Net-(IC9A-X4)") (class "Default")
      (node (ref "IC9") (pin "1") (pinfunction "X4_1") (pintype "bidirectional"))
      (node (ref "P_Y") (pin "P$2") (pinfunction "S_P$2") (pintype "passive"))
    )
    (net (code "53") (name "Net-(IC9A-X5)") (class "Default")
      (node (ref "IC9") (pin "5") (pinfunction "X5_5") (pintype "bidirectional"))
      (node (ref "P_MODA") (pin "P$2") (pinfunction "S_P$2") (pintype "passive"))
    )
    (net (code "54") (name "Net-(IC9A-X6)") (class "Default")
      (node (ref "IC9") (pin "2") (pinfunction "X6_2") (pintype "bidirectional"))
      (node (ref "P_MODB") (pin "P$2") (pinfunction "S_P$2") (pintype "passive"))
    )
    (net (code "55") (name "Net-(IC9A-X7)") (class "Default")
      (node (ref "IC9") (pin "4") (pinfunction "X7_4") (pintype "bidirectional"))
      (node (ref "P_SAMPLE") (pin "P$2") (pinfunction "S_P$2") (pintype "passive"))
    )
    (net (code "56") (name "Net-(J1-3)") (class "Default")
      (node (ref "J1") (pin "P3") (pinfunction "3_P3") (pintype "passive"))
      (node (ref "R5") (pin "1") (pinfunction "1_1") (pintype "passive"))
      (node (ref "R6") (pin "2") (pinfunction "2_2") (pintype "passive"))
      (node (ref "T1") (pin "1") (pinfunction "C_1") (pintype "passive"))
    )
    (net (code "57") (name "Net-(J2-3)") (class "Default")
      (node (ref "J2") (pin "P3") (pinfunction "3_P3") (pintype "passive"))
      (node (ref "R2") (pin "1") (pinfunction "1_1") (pintype "passive"))
      (node (ref "R3") (pin "2") (pinfunction "2_2") (pintype "passive"))
      (node (ref "T2") (pin "1") (pinfunction "C_1") (pintype "passive"))
    )
    (net (code "58") (name "Net-(J32-3)") (class "Default")
      (node (ref "J32") (pin "P3") (pinfunction "3_P3") (pintype "passive"))
      (node (ref "R8") (pin "2") (pinfunction "2_2") (pintype "passive"))
    )
    (net (code "59") (name "Net-(JP1-Pad1)") (class "Default")
      (node (ref "JP1") (pin "1") (pinfunction "1_1") (pintype "passive"))
      (node (ref "JP1") (pin "2") (pinfunction "2_2") (pintype "passive"))
      (node (ref "P2") (pin "2") (pinfunction "2_2") (pintype "bidirectional"))
    )
    (net (code "60") (name "Net-(JP1-Pad10)") (class "Default")
      (node (ref "JP1") (pin "10") (pinfunction "10_10") (pintype "passive"))
      (node (ref "JP1") (pin "9") (pinfunction "9_9") (pintype "passive"))
      (node (ref "P1") (pin "2") (pinfunction "2_2") (pintype "bidirectional"))
    )
    (net (code "61") (name "Net-(JP1-Pad11)") (class "Default")
      (node (ref "JP1") (pin "11") (pinfunction "11_11") (pintype "passive"))
      (node (ref "JP1") (pin "12") (pinfunction "12_12") (pintype "passive"))
      (node (ref "P3") (pin "2") (pinfunction "2_2") (pintype "bidirectional"))
    )
    (net (code "62") (name "Net-(R14-Pad2)") (class "Default")
      (node (ref "R14") (pin "2") (pinfunction "2_2") (pintype "passive"))
      (node (ref "U$2") (pin "23-A9/CRX1/MCLK1") (pinfunction "23-A9/CRX1/MCLK1_23-A9/CRX1/MCLK1") (pintype "bidirectional"))
    )
    (net (code "63") (name "Net-(T1-B)") (class "Default")
      (node (ref "R4") (pin "2") (pinfunction "2_2") (pintype "passive"))
      (node (ref "T1") (pin "2") (pinfunction "B_2") (pintype "passive"))
    )
    (net (code "64") (name "Net-(T2-B)") (class "Default")
      (node (ref "R1") (pin "2") (pinfunction "2_2") (pintype "passive"))
      (node (ref "T2") (pin "2") (pinfunction "B_2") (pintype "passive"))
    )
    (net (code "65") (name "Net-(U2-I2S_LRCLK)") (class "Default")
      (node (ref "U$2") (pin "20-A6/TX5/LRCLK1") (pinfunction "20-A6/TX5/LRCLK1_20-A6/TX5/LRCLK1") (pintype "bidirectional"))
      (node (ref "U2") (pin "23") (pinfunction "I2S_LRCLK_23") (pintype "input"))
    )
    (net (code "66") (name "Net-(U2-I2S_SCLK)") (class "Default")
      (node (ref "U$2") (pin "21-A7/RX5/BCLK1") (pinfunction "21-A7/RX5/BCLK1_21-A7/RX5/BCLK1") (pintype "bidirectional"))
      (node (ref "U2") (pin "24") (pinfunction "I2S_SCLK_24") (pintype "input"))
    )
    (net (code "67") (name "Net-(U2-SYS_MCLK)") (class "Default")
      (node (ref "R14") (pin "1") (pinfunction "1_1") (pintype "passive"))
      (node (ref "U2") (pin "21") (pinfunction "SYS_MCLK_21") (pintype "input"))
    )
    (net (code "68") (name "Net-(U2-VAG)") (class "Default")
      (node (ref "C19") (pin "1") (pinfunction "1_1") (pintype "passive"))
      (node (ref "U2") (pin "10") (pinfunction "VAG_10") (pintype "bidirectional"))
    )
    (net (code "69") (name "Net-(U2-VDDA)") (class "Default")
      (node (ref "C11") (pin "1") (pinfunction "1_1") (pintype "passive"))
      (node (ref "C3") (pin "1") (pinfunction "1_1") (pintype "passive"))
      (node (ref "L1") (pin "1") (pinfunction "1_1") (pintype "passive"))
      (node (ref "U2") (pin "5") (pinfunction "VDDA_5") (pintype "power_in"))
    )
    (net (code "70") (name "Net-(U2-VDDD)") (class "Default")
      (node (ref "C12") (pin "1") (pinfunction "1_1") (pintype "passive"))
      (node (ref "U2") (pin "30") (pinfunction "VDDD_30") (pintype "power_in"))
      (node (ref "U3") (pin "2") (pinfunction "OUT_2") (pintype "power_in"))
    )
    (net (code "71") (name "PAD") (class "Default")
      (node (ref "U2") (pin "33") (pinfunction "PAD_33") (pintype "power_in"))
    )
    (net (code "72") (name "R+") (class "Default")
      (node (ref "R20") (pin "2") (pinfunction "2_2") (pintype "passive"))
      (node (ref "X1") (pin "5") (pinfunction "5_5") (pintype "passive"))
    )
    (net (code "73") (name "R1+") (class "Default")
      (node (ref "IC8") (pin "1") (pinfunction "OUT_1") (pintype "output"))
      (node (ref "IC8") (pin "2") (pinfunction "-IN_2") (pintype "input"))
      (node (ref "R20") (pin "1") (pinfunction "1_1") (pintype "passive"))
    )
    (net (code "74") (name "RX_DOUT") (class "Default")
      (node (ref "U$2") (pin "8-TX2/IN1") (pinfunction "8-TX2/IN1_8-TX2/IN1") (pintype "bidirectional"))
      (node (ref "U2") (pin "25") (pinfunction "I2S_DOUT_25") (pintype "output"))
    )
    (net (code "75") (name "SCK") (class "Default")
      (node (ref "IC7") (pin "4") (pinfunction "SCK_4") (pintype "bidirectional"))
      (node (ref "U$2") (pin "13-SCK/LED") (pinfunction "13-SCK/LED_13-SCK/LED") (pintype "bidirectional"))
    )
    (net (code "76") (name "SCL") (class "Default")
      (node (ref "R17") (pin "1") (pinfunction "1_1") (pintype "passive"))
      (node (ref "U$2") (pin "19-A5/SCL0") (pinfunction "19-A5/SCL0_19-A5/SCL0") (pintype "bidirectional"))
      (node (ref "U2") (pin "29") (pinfunction "CTRL_CLK_29") (pintype "bidirectional"))
    )
    (net (code "77") (name "SDA") (class "Default")
      (node (ref "R15") (pin "1") (pinfunction "1_1") (pintype "passive"))
      (node (ref "U$2") (pin "18-A4/SDA0") (pinfunction "18-A4/SDA0_18-A4/SDA0") (pintype "bidirectional"))
      (node (ref "U2") (pin "27") (pinfunction "CTRL_DATA_27") (pintype "input"))
    )
    (net (code "78") (name "SHUTTER") (class "Default")
      (node (ref "X1") (pin "13") (pinfunction "13_13") (pintype "passive"))
    )
    (net (code "79") (name "SS") (class "Default")
      (node (ref "IC7") (pin "3") (pinfunction "~{CS}_3") (pintype "bidirectional"))
      (node (ref "U$2") (pin "10-CS\\MQSR") (pinfunction "10-CS/MQSR_10-CS\\MQSR") (pintype "bidirectional"))
    )
    (net (code "80") (name "T26") (class "Default")
      (node (ref "R1") (pin "1") (pinfunction "1_1") (pintype "passive"))
      (node (ref "U$2") (pin "26-A12/MOSI1") (pinfunction "26-A12/MOSI1_26-A12/MOSI1") (pintype "bidirectional"))
    )
    (net (code "81") (name "T27") (class "Default")
      (node (ref "R4") (pin "1") (pinfunction "1_1") (pintype "passive"))
      (node (ref "U$2") (pin "27-A13/SCK1") (pinfunction "27-A13/SCK1_27-A13/SCK1") (pintype "bidirectional"))
    )
    (net (code "82") (name "T30") (class "Default")
      (node (ref "C15") (pin "2") (pinfunction "2_2") (pintype "passive"))
      (node (ref "IC6") (pin "1") (pinfunction "OUT_1") (pintype "output"))
      (node (ref "R9") (pin "1") (pinfunction "1_1") (pintype "passive"))
      (node (ref "U$2") (pin "30-CRX3") (pinfunction "30-CRX3_30-CRX3") (pintype "bidirectional"))
    )
    (net (code "83") (name "T38") (class "Default")
      (node (ref "IC1") (pin "12") (pinfunction "X3_12") (pintype "bidirectional"))
      (node (ref "IC1") (pin "2") (pinfunction "X6_2") (pintype "bidirectional"))
      (node (ref "SW_DOWN") (pin "A1") (pinfunction "S_A1") (pintype "passive"))
      (node (ref "SW_DOWN") (pin "A2") (pinfunction "S1_A2") (pintype "passive"))
      (node (ref "SW_PLAY") (pin "A1") (pinfunction "S_A1") (pintype "passive"))
      (node (ref "SW_PLAY") (pin "A2") (pinfunction "S1_A2") (pintype "passive"))
      (node (ref "U$2") (pin "38-A14/CS/IN1") (pinfunction "38-A14/CS/IN1_38-A14/CS/IN1") (pintype "bidirectional"))
    )
    (net (code "84") (name "T39") (class "Default")
      (node (ref "IC1") (pin "4") (pinfunction "X7_4") (pintype "bidirectional"))
      (node (ref "IC1") (pin "5") (pinfunction "X5_5") (pintype "bidirectional"))
      (node (ref "SW_LEFT") (pin "A1") (pinfunction "S_A1") (pintype "passive"))
      (node (ref "SW_LEFT") (pin "A2") (pinfunction "S1_A2") (pintype "passive"))
      (node (ref "SW_RIGHT") (pin "A1") (pinfunction "S_A1") (pintype "passive"))
      (node (ref "SW_UP") (pin "A1") (pinfunction "S_A1") (pintype "passive"))
      (node (ref "SW_UP") (pin "A2") (pinfunction "S1_A2") (pintype "passive"))
      (node (ref "U$2") (pin "39-A15/CS/OUT1A") (pinfunction "39-A15/CS/OUT1A_39-A15/CS/OUT1A") (pintype "bidirectional"))
    )
    (net (code "85") (name "T40") (class "Default")
      (node (ref "U$2") (pin "40-A16/CS1") (pinfunction "40-A16/CS1_40-A16/CS1") (pintype "bidirectional"))
    )
    (net (code "86") (name "T41") (class "Default")
      (node (ref "U$2") (pin "41-A17/MISO1") (pinfunction "41-A17/MISO1_41-A17/MISO1") (pintype "bidirectional"))
    )
    (net (code "87") (name "TB") (class "Default")
      (node (ref "IC8") (pin "10") (pinfunction "+IN_10") (pintype "input"))
      (node (ref "R22") (pin "2") (pinfunction "2_2") (pintype "passive"))
      (node (ref "U$2") (pin "6-OUT1D") (pinfunction "6-OUT1D_6-OUT1D") (pintype "bidirectional"))
    )
    (net (code "88") (name "TG") (class "Default")
      (node (ref "IC8") (pin "5") (pinfunction "+IN_5") (pintype "input"))
      (node (ref "R23") (pin "2") (pinfunction "2_2") (pintype "passive"))
      (node (ref "U$2") (pin "9-OUT1C") (pinfunction "9-OUT1C_9-OUT1C") (pintype "bidirectional"))
    )
    (net (code "89") (name "TR") (class "Default")
      (node (ref "IC8") (pin "3") (pinfunction "+IN_3") (pintype "input"))
      (node (ref "R25") (pin "2") (pinfunction "2_2") (pintype "passive"))
      (node (ref "U$2") (pin "32-OUT1B") (pinfunction "32-OUT1B_32-OUT1B") (pintype "bidirectional"))
    )
    (net (code "90") (name "TX_DIN") (class "Default")
      (node (ref "U$2") (pin "7-RX2/OUT1A") (pinfunction "7-RX2/OUT1A_7-RX2/OUT1A") (pintype "bidirectional"))
      (node (ref "U2") (pin "26") (pinfunction "I2S_DIN_26") (pintype "input"))
    )
    (net (code "91") (name "VCC") (class "Default")
      (node (ref "R2") (pin "2") (pinfunction "2_2") (pintype "passive"))
      (node (ref "R5") (pin "2") (pinfunction "2_2") (pintype "passive"))
    )
    (net (code "92") (name "VREF5") (class "Default")
      (node (ref "C17") (pin "1") (pinfunction "1_1") (pintype "passive"))
      (node (ref "IC3") (pin "13") (pinfunction "-IN_13") (pintype "input"))
      (node (ref "IC3") (pin "14") (pinfunction "OUT_14") (pintype "output"))
      (node (ref "IC7") (pin "11") (pinfunction "VREFB_11") (pintype "bidirectional"))
      (node (ref "IC7") (pin "13") (pinfunction "VREFA_13") (pintype "bidirectional"))
    )
    (net (code "93") (name "X+") (class "Default")
      (node (ref "R35") (pin "2") (pinfunction "2_2") (pintype "passive"))
      (node (ref "X1") (pin "1") (pinfunction "1_1") (pintype "passive"))
    )
    (net (code "94") (name "X-") (class "Default")
      (node (ref "R24") (pin "2") (pinfunction "2_2") (pintype "passive"))
      (node (ref "X1") (pin "14") (pinfunction "14_14") (pintype "passive"))
    )
    (net (code "95") (name "X2") (class "Default")
      (node (ref "IC2") (pin "3") (pinfunction "+IN_3") (pintype "input"))
      (node (ref "IC4") (pin "7") (pinfunction "OUT_7") (pintype "output"))
      (node (ref "R27") (pin "2") (pinfunction "2_2") (pintype "passive"))
      (node (ref "R33") (pin "1") (pinfunction "1_1") (pintype "passive"))
    )
    (net (code "96") (name "Y+") (class "Default")
      (node (ref "R21") (pin "2") (pinfunction "2_2") (pintype "passive"))
      (node (ref "X1") (pin "2") (pinfunction "2_2") (pintype "passive"))
    )
    (net (code "97") (name "Y-") (class "Default")
      (node (ref "R16") (pin "2") (pinfunction "2_2") (pintype "passive"))
      (node (ref "X1") (pin "15") (pinfunction "15_15") (pintype "passive"))
    )
    (net (code "98") (name "Y2") (class "Default")
      (node (ref "IC2") (pin "10") (pinfunction "+IN_10") (pintype "input"))
      (node (ref "IC4") (pin "1") (pinfunction "OUT_1") (pintype "output"))
      (node (ref "R29") (pin "2") (pinfunction "2_2") (pintype "passive"))
      (node (ref "R31") (pin "1") (pinfunction "1_1") (pintype "passive"))
    )
    (net (code "99") (name "unconnected-(IC7-NC_1-Pad2)") (class "Default")
      (node (ref "IC7") (pin "2") (pinfunction "NC_1_2") (pintype "bidirectional"))
    )
    (net (code "100") (name "unconnected-(IC7-NC_2-Pad6)") (class "Default")
      (node (ref "IC7") (pin "6") (pinfunction "NC_2_6") (pintype "bidirectional"))
    )
    (net (code "101") (name "unconnected-(IC7-NC_3-Pad7)") (class "Default")
      (node (ref "IC7") (pin "7") (pinfunction "NC_3_7") (pintype "bidirectional"))
    )
    (net (code "102") (name "unconnected-(J1-2-PadP2)") (class "Default")
      (node (ref "J1") (pin "P2") (pinfunction "2_P2") (pintype "passive"))
    )
    (net (code "103") (name "unconnected-(J2-2-PadP2)") (class "Default")
      (node (ref "J2") (pin "P2") (pinfunction "2_P2") (pintype "passive"))
    )
    (net (code "104") (name "unconnected-(JP1-Pad13)") (class "Default")
      (node (ref "JP1") (pin "13") (pinfunction "13_13") (pintype "passive"))
    )
    (net (code "105") (name "unconnected-(JP1-Pad14)") (class "Default")
      (node (ref "JP1") (pin "14") (pinfunction "14_14") (pintype "passive"))
    )
    (net (code "106") (name "unconnected-(JP1-Pad15)") (class "Default")
      (node (ref "JP1") (pin "15") (pinfunction "15_15") (pintype "passive"))
    )
    (net (code "107") (name "unconnected-(JP1-Pad16)") (class "Default")
      (node (ref "JP1") (pin "16") (pinfunction "16_16") (pintype "passive"))
    )
    (net (code "108") (name "unconnected-(JP2-Pad1)") (class "Default")
      (node (ref "JP2") (pin "1") (pinfunction "1_1") (pintype "passive"))
    )
    (net (code "109") (name "unconnected-(SW_BLANK-P-PadB1)") (class "Default")
      (node (ref "SW_BLANK") (pin "B1") (pinfunction "P_B1") (pintype "passive"))
    )
    (net (code "110") (name "unconnected-(SW_BLANK-S-PadA1)") (class "Default")
      (node (ref "SW_BLANK") (pin "A1") (pinfunction "S_A1") (pintype "passive"))
    )
    (net (code "111") (name "unconnected-(SW_RECORD-P-PadB1)") (class "Default")
      (node (ref "SW_RECORD") (pin "B1") (pinfunction "P_B1") (pintype "passive"))
    )
    (net (code "112") (name "unconnected-(SW_RECORD-S-PadA1)") (class "Default")
      (node (ref "SW_RECORD") (pin "A1") (pinfunction "S_A1") (pintype "passive"))
    )
    (net (code "113") (name "unconnected-(SW_RIGHT-P-PadB1)") (class "Default")
      (node (ref "SW_RIGHT") (pin "B1") (pinfunction "P_B1") (pintype "passive"))
    )
    (net (code "114") (name "unconnected-(U$2-5V-Pad+5V)") (class "Default")
      (node (ref "U$2") (pin "+5V") (pinfunction "5V_+5V") (pintype "bidirectional"))
    )
    (net (code "115") (name "unconnected-(U$2-35{slash}TX8-Pad35-TX8)") (class "Default")
      (node (ref "U$2") (pin "35-TX8") (pinfunction "35/TX8_35-TX8") (pintype "bidirectional"))
    )
    (net (code "116") (name "unconnected-(U$2-Pad0-RX1{slash}CS1{slash}CRX2)") (class "Default")
      (node (ref "U$2") (pin "0-RX1/CS1/CRX2") (pinfunction "0-RX1/CS1/CRX2_0-RX1/CS1/CRX2") (pintype "bidirectional"))
    )
    (net (code "117") (name "unconnected-(U$2-Pad1-TX1{slash}MISO1{slash}CTX2)") (class "Default")
      (node (ref "U$2") (pin "1-TX1/MISO1/CTX2") (pinfunction "1-TX1/MISO1/CTX2_1-TX1/MISO1/CTX2") (pintype "bidirectional"))
    )
    (net (code "118") (name "unconnected-(U$2-Pad2-OUT2)") (class "Default")
      (node (ref "U$2") (pin "2-OUT2") (pinfunction "2-OUT2_2-OUT2") (pintype "bidirectional"))
    )
    (net (code "119") (name "unconnected-(U$2-Pad3-LRCLK2)") (class "Default")
      (node (ref "U$2") (pin "3-LRCLK2") (pinfunction "3-LRCLK2_3-LRCLK2") (pintype "bidirectional"))
    )
    (net (code "120") (name "unconnected-(U$2-Pad3V3-1)") (class "Default")
      (node (ref "U$2") (pin "3V3-1") (pinfunction "3V3-1_3V3-1") (pintype "bidirectional"))
    )
    (net (code "121") (name "unconnected-(U$2-Pad3V3-2)") (class "Default")
      (node (ref "U$2") (pin "3V3-2") (pinfunction "3V3-2_3V3-2") (pintype "bidirectional"))
    )
    (net (code "122") (name "unconnected-(U$2-Pad3V3-3)") (class "Default")
      (node (ref "U$2") (pin "3V3-3") (pinfunction "3V3-3_3V3-3") (pintype "bidirectional"))
    )
    (net (code "123") (name "unconnected-(U$2-Pad4-BCLK2)") (class "Default")
      (node (ref "U$2") (pin "4-BCLK2") (pinfunction "4-BCLK2_4-BCLK2") (pintype "bidirectional"))
    )
    (net (code "124") (name "unconnected-(U$2-Pad5-IN2)") (class "Default")
      (node (ref "U$2") (pin "5-IN2") (pinfunction "5-IN2_5-IN2") (pintype "bidirectional"))
    )
    (net (code "125") (name "unconnected-(U$2-Pad14-A0{slash}TX3{slash}SPDIF_OUT)") (class "Default")
      (node (ref "U$2") (pin "14-A0/TX3/SPDIF_OUT") (pinfunction "14-A0/TX3/SPDIF_OUT_14-A0/TX3/SPDIF_OUT") (pintype "bidirectional"))
    )
    (net (code "126") (name "unconnected-(U$2-Pad15-A1{slash}RX3{slash}SPDIF_IN)") (class "Default")
      (node (ref "U$2") (pin "15-A1/RX3/SPDIF_IN") (pinfunction "15-A1/RX3/SPDIF_IN_15-A1/RX3/SPDIF_IN") (pintype "bidirectional"))
    )
    (net (code "127") (name "unconnected-(U$2-Pad16-A2{slash}RX4{slash}SCL1)") (class "Default")
      (node (ref "U$2") (pin "16-A2/RX4/SCL1") (pinfunction "16-A2/RX4/SCL1_16-A2/RX4/SCL1") (pintype "bidirectional"))
    )
    (net (code "128") (name "unconnected-(U$2-Pad17-A3{slash}TX4{slash}SDA1)") (class "Default")
      (node (ref "U$2") (pin "17-A3/TX4/SDA1") (pinfunction "17-A3/TX4/SDA1_17-A3/TX4/SDA1") (pintype "bidirectional"))
    )
    (net (code "129") (name "unconnected-(U$2-Pad22-A8{slash}CTX1)") (class "Default")
      (node (ref "U$2") (pin "22-A8/CTX1") (pinfunction "22-A8/CTX1_22-A8/CTX1") (pintype "bidirectional"))
    )
    (net (code "130") (name "unconnected-(U$2-Pad24-A10{slash}TX6{slash}SCL2)") (class "Default")
      (node (ref "U$2") (pin "24-A10/TX6/SCL2") (pinfunction "24-A10/TX6/SCL2_24-A10/TX6/SCL2") (pintype "bidirectional"))
    )
    (net (code "131") (name "unconnected-(U$2-Pad25-A11{slash}RX6{slash}SDA2)") (class "Default")
      (node (ref "U$2") (pin "25-A11/RX6/SDA2") (pinfunction "25-A11/RX6/SDA2_25-A11/RX6/SDA2") (pintype "bidirectional"))
    )
    (net (code "132") (name "unconnected-(U$2-Pad28-RX7)") (class "Default")
      (node (ref "U$2") (pin "28-RX7") (pinfunction "28-RX7_28-RX7") (pintype "bidirectional"))
    )
    (net (code "133") (name "unconnected-(U$2-Pad29-TX7)") (class "Default")
      (node (ref "U$2") (pin "29-TX7") (pinfunction "29-TX7_29-TX7") (pintype "bidirectional"))
    )
    (net (code "134") (name "unconnected-(U$2-Pad31-CTX3)") (class "Default")
      (node (ref "U$2") (pin "31-CTX3") (pinfunction "31-CTX3_31-CTX3") (pintype "bidirectional"))
    )
    (net (code "135") (name "unconnected-(U$2-Pad33-MCLK2)") (class "Default")
      (node (ref "U$2") (pin "33-MCLK2") (pinfunction "33-MCLK2_33-MCLK2") (pintype "bidirectional"))
    )
    (net (code "136") (name "unconnected-(U$2-Pad34-RX8)") (class "Default")
      (node (ref "U$2") (pin "34-RX8") (pinfunction "34-RX8_34-RX8") (pintype "bidirectional"))
    )
    (net (code "137") (name "unconnected-(U$2-Pad36-PWM)") (class "Default")
      (node (ref "U$2") (pin "36-PWM") (pinfunction "36-PWM_36-PWM") (pintype "bidirectional"))
    )
    (net (code "138") (name "unconnected-(U$2-Pad37-PWM)") (class "Default")
      (node (ref "U$2") (pin "37-PWM") (pinfunction "37-PWM_37-PWM") (pintype "bidirectional"))
    )
    (net (code "139") (name "unconnected-(U$2-PadDM)") (class "Default")
      (node (ref "U$2") (pin "DM") (pinfunction "DM_DM") (pintype "bidirectional"))
    )
    (net (code "140") (name "unconnected-(U$2-PadDP)") (class "Default")
      (node (ref "U$2") (pin "DP") (pinfunction "DP_DP") (pintype "bidirectional"))
    )
    (net (code "141") (name "unconnected-(U$2-PadGND1)") (class "Default")
      (node (ref "U$2") (pin "GND1") (pinfunction "GND1_GND1") (pintype "bidirectional"))
    )
    (net (code "142") (name "unconnected-(U$2-PadGND2)") (class "Default")
      (node (ref "U$2") (pin "GND2") (pinfunction "GND2_GND2") (pintype "bidirectional"))
    )
    (net (code "143") (name "unconnected-(U$2-PadGND3)") (class "Default")
      (node (ref "U$2") (pin "GND3") (pinfunction "GND3_GND3") (pintype "bidirectional"))
    )
    (net (code "144") (name "unconnected-(U$2-PadGND4)") (class "Default")
      (node (ref "U$2") (pin "GND4") (pinfunction "GND4_GND4") (pintype "bidirectional"))
    )
    (net (code "145") (name "unconnected-(U$2-PadGND5)") (class "Default")
      (node (ref "U$2") (pin "GND5") (pinfunction "GND5_GND5") (pintype "bidirectional"))
    )
    (net (code "146") (name "unconnected-(U$2-PadGND6)") (class "Default")
      (node (ref "U$2") (pin "GND6") (pinfunction "GND6_GND6") (pintype "bidirectional"))
    )
    (net (code "147") (name "unconnected-(U$2-PadON{slash}OFF)") (class "Default")
      (node (ref "U$2") (pin "ON/OFF") (pinfunction "ON/OFF_ON/OFF") (pintype "bidirectional"))
    )
    (net (code "148") (name "unconnected-(U$2-PadPROGRAM)") (class "Default")
      (node (ref "U$2") (pin "PROGRAM") (pinfunction "PROGRAM_PROGRAM") (pintype "bidirectional"))
    )
    (net (code "149") (name "unconnected-(U$2-PadVBAT)") (class "Default")
      (node (ref "U$2") (pin "VBAT") (pinfunction "VBAT_VBAT") (pintype "bidirectional"))
    )
    (net (code "150") (name "unconnected-(U$2-PadVUSB)") (class "Default")
      (node (ref "U$2") (pin "VUSB") (pinfunction "VUSB_VUSB") (pintype "bidirectional"))
    )
    (net (code "151") (name "unconnected-(U2-CPFILT-Pad18)") (class "Default")
      (node (ref "U2") (pin "18") (pinfunction "CPFILT_18") (pintype "bidirectional"))
    )
    (net (code "152") (name "unconnected-(U2-HP_L-Pad6)") (class "Default")
      (node (ref "U2") (pin "6") (pinfunction "HP_L_6") (pintype "output"))
    )
    (net (code "153") (name "unconnected-(U2-HP_R-Pad2)") (class "Default")
      (node (ref "U2") (pin "2") (pinfunction "HP_R_2") (pintype "output"))
    )
    (net (code "154") (name "unconnected-(U2-MIC-Pad15)") (class "Default")
      (node (ref "U2") (pin "15") (pinfunction "MIC_15") (pintype "input"))
    )
    (net (code "155") (name "unconnected-(U2-MIC_BIAS-Pad16)") (class "Default")
      (node (ref "U2") (pin "16") (pinfunction "MIC_BIAS_16") (pintype "bidirectional"))
    )
    (net (code "156") (name "unconnected-(U2-NC_8-Pad8)") (class "Default")
      (node (ref "U2") (pin "8") (pinfunction "NC_8_8") (pintype "passive"))
    )
    (net (code "157") (name "unconnected-(U2-NC_9-Pad9)") (class "Default")
      (node (ref "U2") (pin "9") (pinfunction "NC_9_9") (pintype "passive"))
    )
    (net (code "158") (name "unconnected-(U2-NC_17-Pad17)") (class "Default")
      (node (ref "U2") (pin "17") (pinfunction "NC_17_17") (pintype "passive"))
    )
    (net (code "159") (name "unconnected-(U2-NC_19-Pad19)") (class "Default")
      (node (ref "U2") (pin "19") (pinfunction "NC_19_19") (pintype "passive"))
    )
    (net (code "160") (name "unconnected-(U2-NC_22-Pad22)") (class "Default")
      (node (ref "U2") (pin "22") (pinfunction "NC_22_22") (pintype "passive"))
    )
    (net (code "161") (name "unconnected-(U2-NC_28-Pad28)") (class "Default")
      (node (ref "U2") (pin "28") (pinfunction "NC_28_28") (pintype "passive"))
    )
    (net (code "162") (name "unconnected-(X1-Pad3)") (class "Default")
      (node (ref "X1") (pin "3") (pinfunction "3_3") (pintype "passive"))
    )
    (net (code "163") (name "unconnected-(X1-Pad8)") (class "Default")
      (node (ref "X1") (pin "8") (pinfunction "8_8") (pintype "passive"))
    )
    (net (code "164") (name "unconnected-(X1-Pad9)") (class "Default")
      (node (ref "X1") (pin "9") (pinfunction "9_9") (pintype "passive"))
    )
    (net (code "165") (name "unconnected-(X1-Pad10)") (class "Default")
      (node (ref "X1") (pin "10") (pinfunction "10_10") (pintype "passive"))
    )
    (net (code "166") (name "unconnected-(X1-Pad11)") (class "Default")
      (node (ref "X1") (pin "11") (pinfunction "11_11") (pintype "passive"))
    )
    (net (code "167") (name "unconnected-(X1-Pad12)") (class "Default")
      (node (ref "X1") (pin "12") (pinfunction "12_12") (pintype "passive"))
    )
    (net (code "168") (name "unconnected-(X1-Pad16)") (class "Default")
      (node (ref "X1") (pin "16") (pinfunction "16_16") (pintype "passive"))
    )
    (net (code "169") (name "unconnected-(X1-Pad21)") (class "Default")
      (node (ref "X1") (pin "21") (pinfunction "21_21") (pintype "passive"))
    )
    (net (code "170") (name "unconnected-(X1-Pad22)") (class "Default")
      (node (ref "X1") (pin "22") (pinfunction "22_22") (pintype "passive"))
    )
    (net (code "171") (name "unconnected-(X1-Pad23)") (class "Default")
      (node (ref "X1") (pin "23") (pinfunction "23_23") (pintype "passive"))
    )
    (net (code "172") (name "unconnected-(X1-Pad24)") (class "Default")
      (node (ref "X1") (pin "24") (pinfunction "24_24") (pintype "passive"))
    )
    (net (code "173") (name "~{LDAC}") (class "Default")
      (node (ref "IC7") (pin "8") (pinfunction "~{LDAC}_8") (pintype "bidirectional"))
    )
  )
)
